# Diag_586220_Cassette.net
KiCad netlist of a schematic drawn in EAGLE
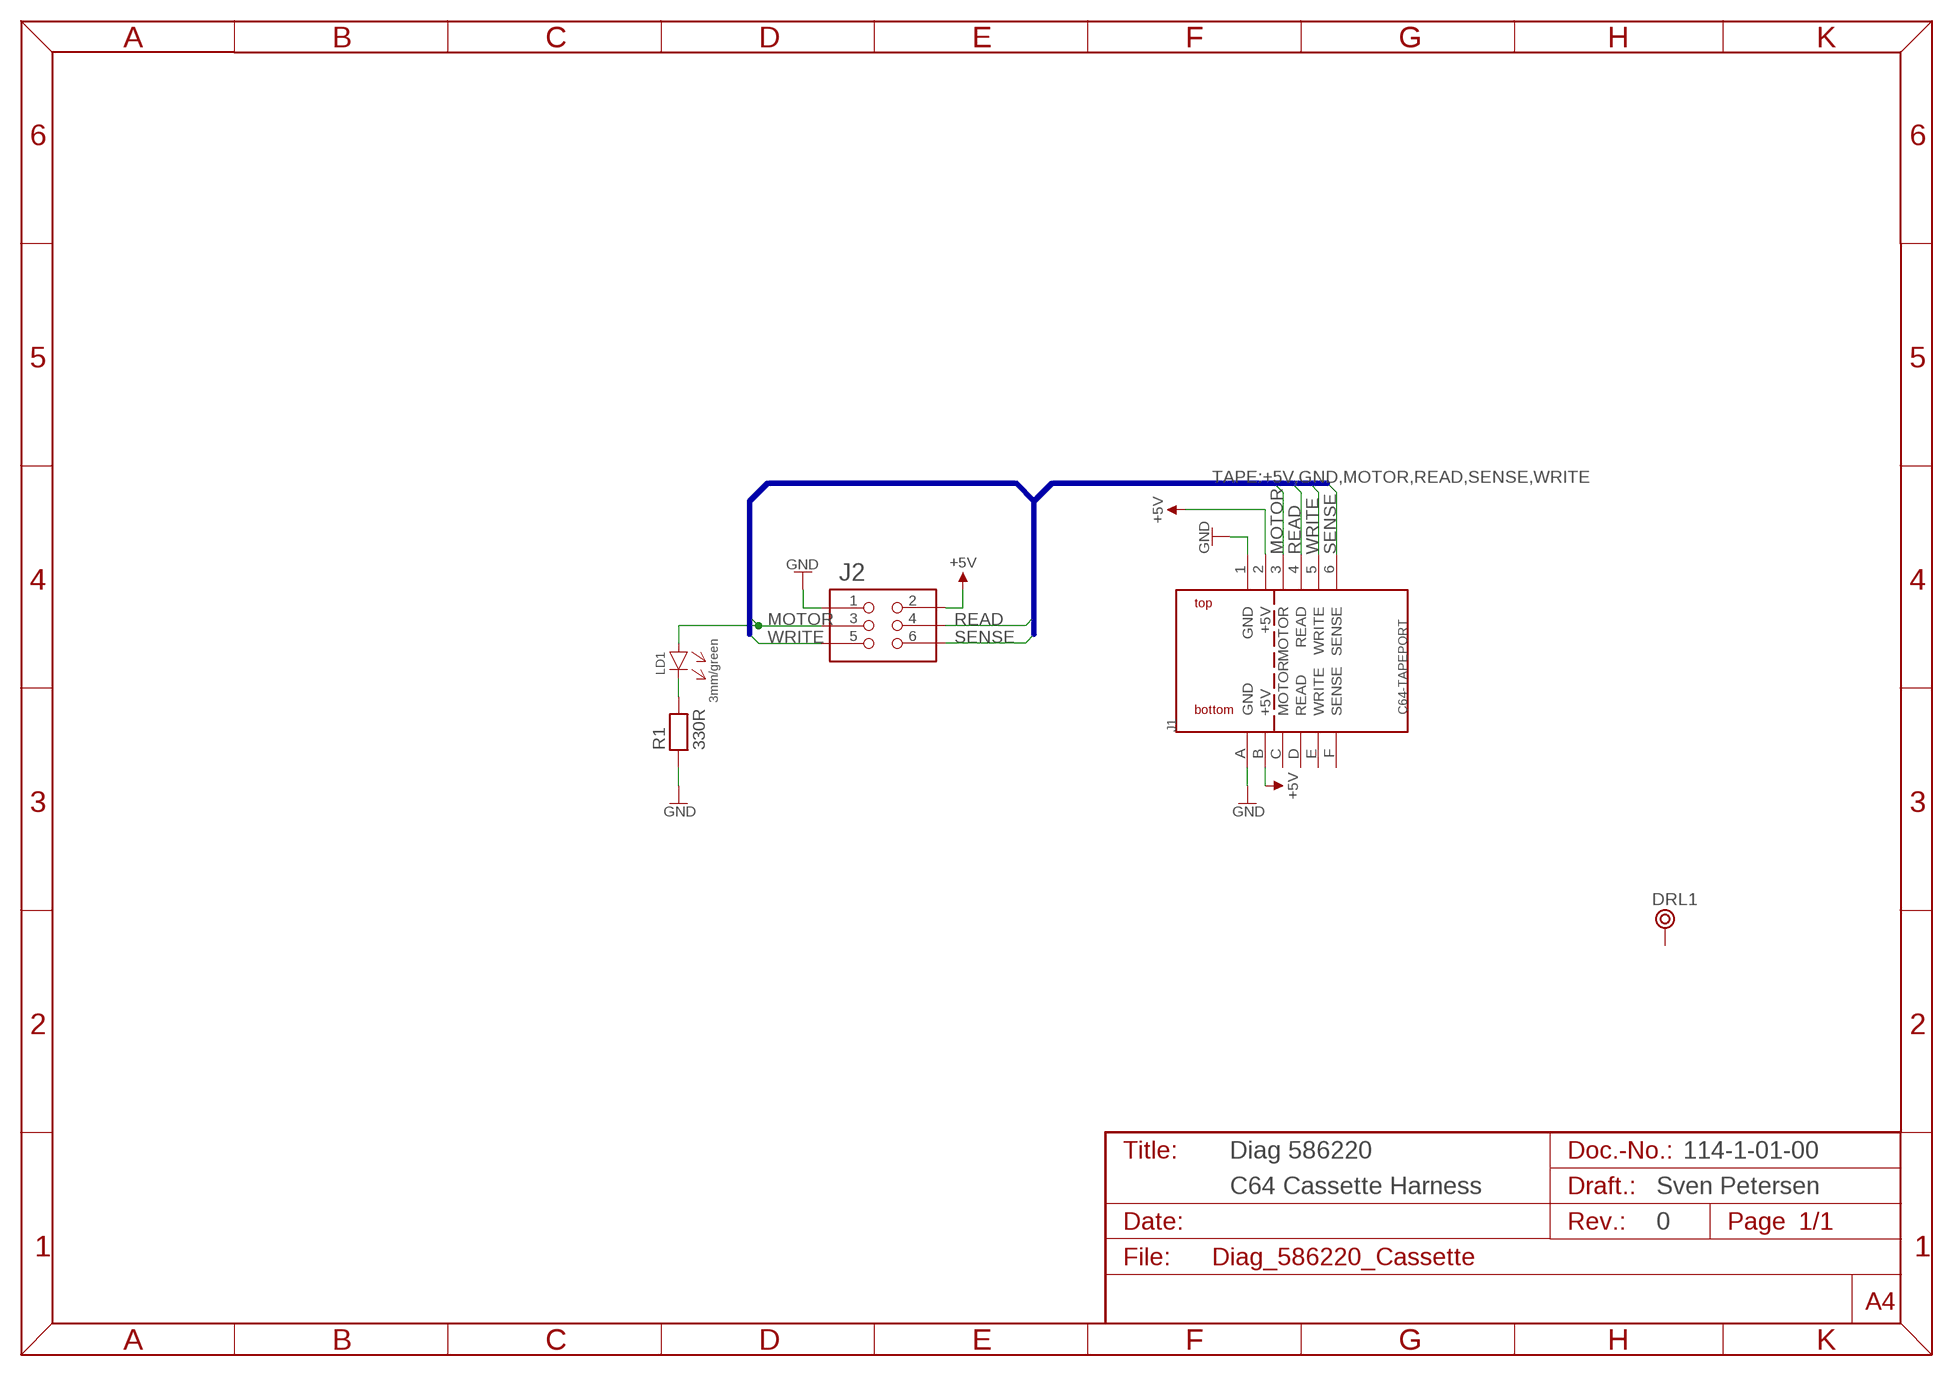
[diagram p0: schematic, sheet 1]

(export (version "E")
  (design (tool "Eeschema 10.0.6"))
  (components
    (comp (ref "DRL1")
      (value "BOHR3,5")
      (footprint "eagle-import:BOHR3,5")
      (libsource (lib "eagle-import") (part "BOHR3,5"))
    )
    (comp (ref "J1")
      (value "C64-TAPEPORT")
      (footprint "eagle-import:TAPEPORT")
      (libsource (lib "eagle-import") (part "C64-TAPEPORT"))
    )
    (comp (ref "J2")
      (value "2X03WV")
      (footprint "eagle-import:2X03WV")
      (libsource (lib "eagle-import") (part "2X03WV"))
    )
    (comp (ref "LD1")
      (value "3mm/green")
      (footprint "eagle-import:3MM")
      (libsource (lib "eagle-import") (part "3MM"))
    )
    (comp (ref "R1")
      (value "330R")
      (footprint "eagle-import:RS-2,5")
      (libsource (lib "eagle-import") (part "RES01"))
    )
  )
  (nets
    (net (code "2") (name "+5V") (class "Default")
      (node (ref "J1") (pin "2") (pinfunction "+5V_2") (pintype "power_in"))
      (node (ref "J1") (pin "B") (pinfunction "+5V_B") (pintype "power_in"))
      (node (ref "J2") (pin "2") (pinfunction "2_2") (pintype "passive"))
    )
    (net (code "3") (name "/MOTOR") (class "Default")
      (node (ref "J1") (pin "3") (pinfunction "MOTOR_3") (pintype "output"))
      (node (ref "J2") (pin "3") (pinfunction "3_3") (pintype "passive"))
      (node (ref "LD1") (pin "A") (pinfunction "A_A") (pintype "bidirectional"))
    )
    (net (code "4") (name "/READ") (class "Default")
      (node (ref "J1") (pin "4") (pinfunction "READ_4") (pintype "input"))
      (node (ref "J2") (pin "4") (pinfunction "4_4") (pintype "passive"))
    )
    (net (code "5") (name "/SENSE") (class "Default")
      (node (ref "J1") (pin "6") (pinfunction "SENSE_6") (pintype "input"))
      (node (ref "J2") (pin "6") (pinfunction "6_6") (pintype "passive"))
    )
    (net (code "6") (name "/WRITE") (class "Default")
      (node (ref "J1") (pin "5") (pinfunction "WRITE_5") (pintype "output"))
      (node (ref "J2") (pin "5") (pinfunction "5_5") (pintype "passive"))
    )
    (net (code "8") (name "GND") (class "Default")
      (node (ref "J1") (pin "1") (pinfunction "GND_1") (pintype "power_in"))
      (node (ref "J1") (pin "A") (pinfunction "GND_A") (pintype "power_in"))
      (node (ref "J2") (pin "1") (pinfunction "1_1") (pintype "passive"))
      (node (ref "R1") (pin "1") (pinfunction "1_1") (pintype "passive"))
    )
    (net (code "9") (name "Net-(LD1-K)") (class "Default")
      (node (ref "LD1") (pin "C") (pinfunction "K_C") (pintype "bidirectional"))
      (node (ref "R1") (pin "2") (pinfunction "2_2") (pintype "passive"))
    )
    (net (code "10") (name "unconnected-(DRL1-PadP$1)") (class "Default")
      (node (ref "DRL1") (pin "P$1") (pinfunction "P$1_P$1") (pintype "passive"))
    )
    (net (code "11") (name "unconnected-(J1-MOTOR-PadC)") (class "Default")
      (node (ref "J1") (pin "C") (pinfunction "MOTOR_C") (pintype "output"))
    )
    (net (code "12") (name "unconnected-(J1-READ-PadD)") (class "Default")
      (node (ref "J1") (pin "D") (pinfunction "READ_D") (pintype "input"))
    )
    (net (code "13") (name "unconnected-(J1-SENSE-PadF)") (class "Default")
      (node (ref "J1") (pin "F") (pinfunction "SENSE_F") (pintype "input"))
    )
    (net (code "14") (name "unconnected-(J1-WRITE-PadE)") (class "Default")
      (node (ref "J1") (pin "E") (pinfunction "WRITE_E") (pintype "output"))
    )
  )
)
